# programming_module.net
KiCad netlist of a schematic drawn in Altium Designer
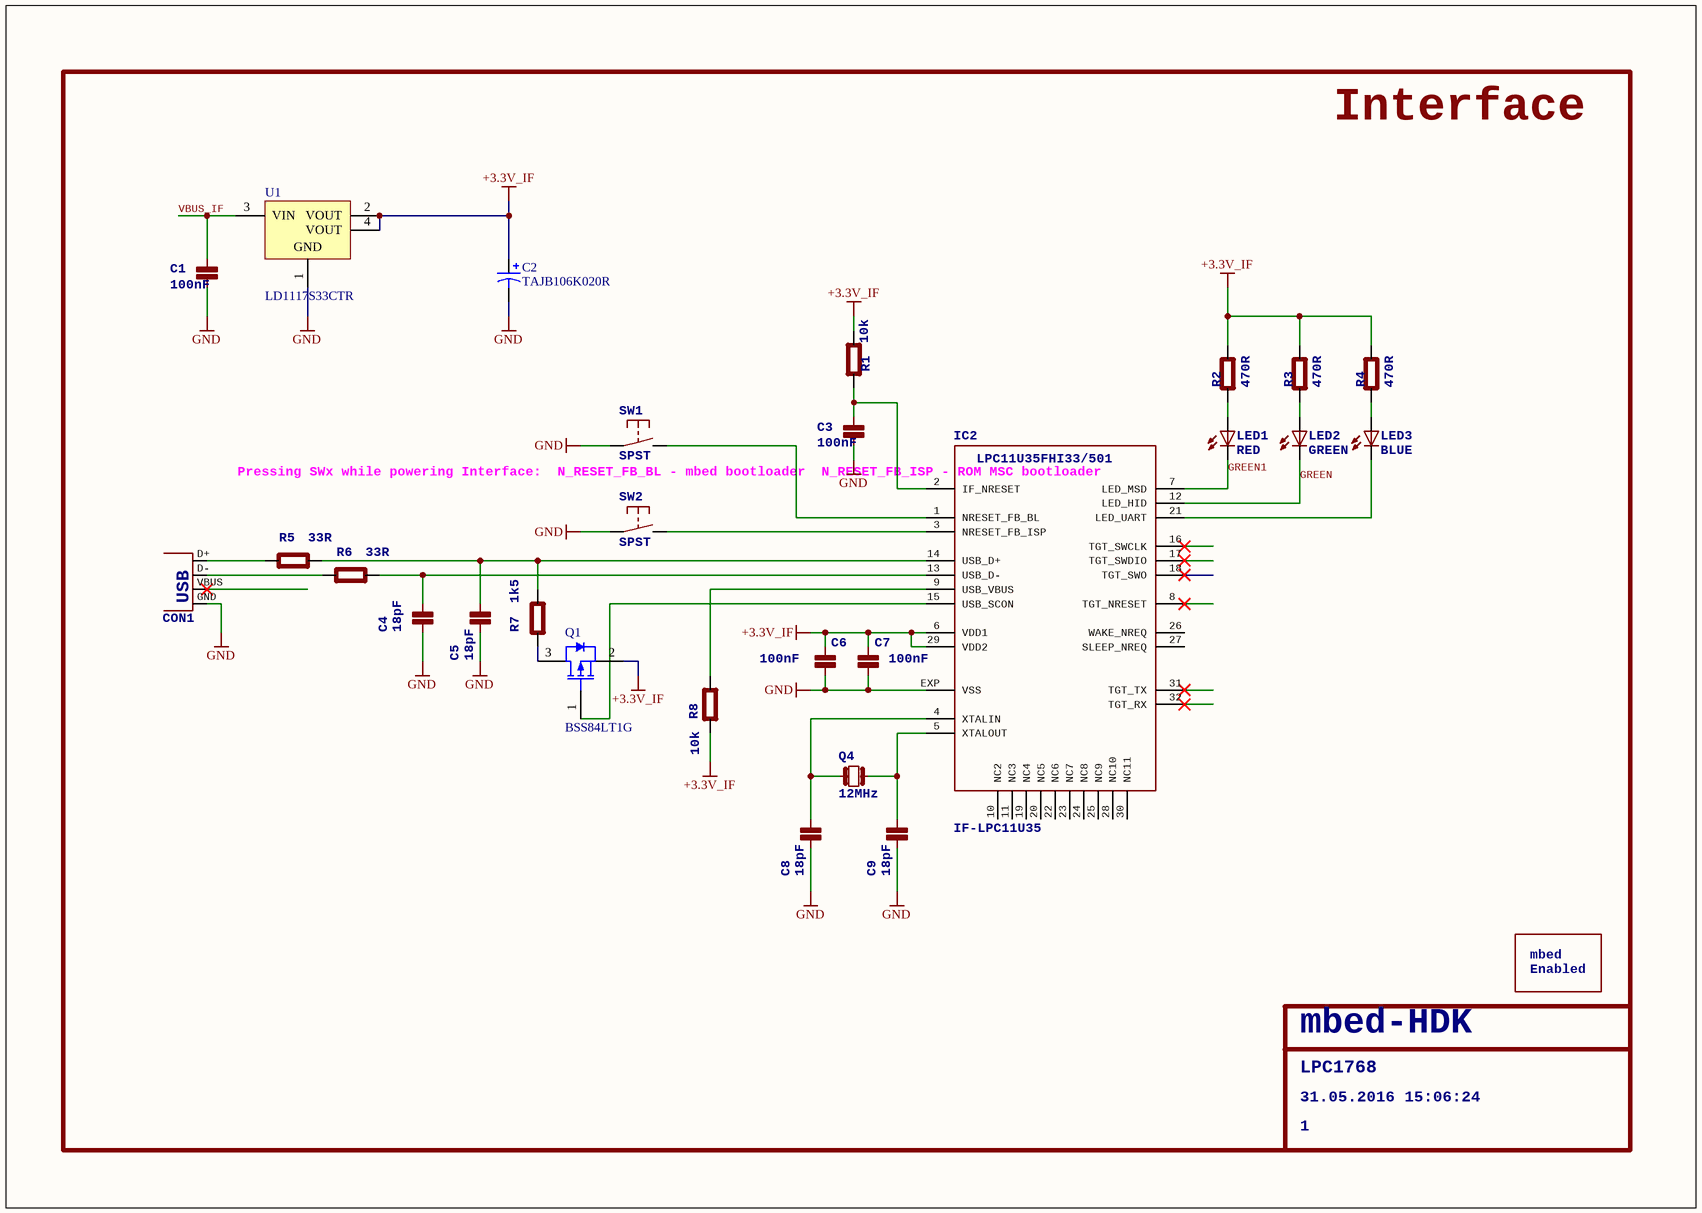
[diagram p0: programming_module.SchDoc]

(export (version "E")
  (design (tool "Eeschema 10.0.6"))
  (components
    (comp (ref "C1") (value "100nF") (footprint "0603") (libsource (lib "") (part "C0603_1")))
    (comp (ref "C2")
      (value "TAJB106K020R")
      (footprint "AVX-CAPC3528_V")
      (description "Capacitor, Tantalum, 10uF 10% 20V MCCT-B (3528)")
      (fields (field (name "MANUFACTURER") "AVX") (field (name "TOLERANCE") "10%"))
      (libsource (lib "Altium Content Vault") (part "AVX-CAP-P-2"))
    )
    (comp (ref "C3") (value "100nF") (footprint "0603") (libsource (lib "") (part "C0603_1")))
    (comp (ref "C4") (value "18pF") (footprint "0603") (libsource (lib "mbed-HDK") (part "C0603")))
    (comp (ref "C5") (value "18pF") (footprint "0603") (libsource (lib "mbed-HDK") (part "C0603")))
    (comp (ref "C6") (value "100nF") (footprint "0603") (libsource (lib "") (part "C0603_1")))
    (comp (ref "C7") (value "100nF") (footprint "0603") (libsource (lib "") (part "C0603_1")))
    (comp (ref "C8") (value "18pF") (footprint "0603") (libsource (lib "mbed-HDK") (part "C0603")))
    (comp (ref "C9") (value "18pF") (footprint "0603") (libsource (lib "mbed-HDK") (part "C0603")))
    (comp (ref "CON1")
      (value "USB-MB-S")
      (footprint "USB-MB-S")
      (description "USB Connectors")
      (fields (field (name "USB") "USB"))
      (libsource (lib "mbed-HDK") (part "USB-MB-S"))
    )
    (comp (ref "IC2")
      (value "IF-LPC11U35")
      (footprint "HVQFN33")
      (fields (field (name "LPC11U35FHI33/501") "LPC11U35FHI33/501"))
      (libsource (lib "mbed-HDK") (part "IF-LPC11U35"))
    )
    (comp (ref "LED1") (value "RED") (footprint "CHIPLED_0603") (libsource (lib "mbed-HDK") (part "LED0603")))
    (comp (ref "LED2")
      (value "GREEN")
      (footprint "CHIPLED_0603")
      (libsource (lib "mbed-HDK") (part "LED0603"))
    )
    (comp (ref "LED3")
      (value "BLUE")
      (footprint "CHIPLED_0603")
      (libsource (lib "mbed-HDK") (part "LED0603"))
    )
    (comp (ref "Q1")
      (value "BSS84LT1G")
      (footprint "ONSC-SOT-23-3-318-08_V")
      (description "Power MOSFET Single P-Channel, -50 V, 10 Ohm, 3-Pin SOT-23, Pb-Free, Tape and Reel")
      (fields (field (name "MANUFACTURER") "On Semiconductor"))
      (libsource (lib "Altium Content Vault") (part "ONSC-PMOS-G1S2D3-3_D"))
    )
    (comp (ref "Q4") (value "12MHz") (footprint "HC49UP") (libsource (lib "mbed-HDK") (part "Q_HC49UP")))
    (comp (ref "R1") (value "10k") (footprint "0603") (libsource (lib "mbed-HDK") (part "R0603")))
    (comp (ref "R2") (value "470R") (footprint "0603") (libsource (lib "mbed-HDK") (part "R0603")))
    (comp (ref "R3") (value "470R") (footprint "0603") (libsource (lib "mbed-HDK") (part "R0603")))
    (comp (ref "R4") (value "470R") (footprint "0603") (libsource (lib "mbed-HDK") (part "R0603")))
    (comp (ref "R5") (value "33R") (footprint "0603") (libsource (lib "mbed-HDK") (part "R0603")))
    (comp (ref "R6") (value "33R") (footprint "0603") (libsource (lib "mbed-HDK") (part "R0603")))
    (comp (ref "R7") (value "1k5") (footprint "0603") (libsource (lib "mbed-HDK") (part "R0603")))
    (comp (ref "R8") (value "10k") (footprint "0603") (libsource (lib "mbed-HDK") (part "R0603")))
    (comp (ref "SS1")
      (value "MBED-ENABLED-LOGOMEDIUM")
      (footprint "MBED-ENABLED-LOGO-500X500-MIL")
      (fields (field (name "MBED") "mbed") (field (name "ENABLED") "Enabled"))
      (libsource (lib "mbed-HDK") (part "MBED-ENABLED-LOGOMEDIUM"))
    )
    (comp (ref "SW1") (value "SPST") (footprint "DTSM-32S-B") (libsource (lib "mbed-HDK") (part "SPST")))
    (comp (ref "SW2") (value "SPST") (footprint "DTSM-32S-B") (libsource (lib "mbed-HDK") (part "SPST")))
    (comp (ref "U1")
      (value "LD1117S33CTR")
      (footprint "SOT-223_L")
      (description "Fixed Low Drop Positive Voltage Regulator, 3.3V, 4-Pin SOT-223, Tape and Reel")
      (libsource (lib "Altium Content Vault") (part "PM-REG-LD1117-SOT4"))
    )
  )
  (nets
    (net (code "1") (name "+3.3V_IF") (class "Default")
      (node (ref "C2") (pin "1") (pinfunction "1_1") (pintype "passive"))
      (node (ref "C6") (pin "1") (pinfunction "P$1_1") (pintype "passive"))
      (node (ref "C7") (pin "1") (pinfunction "P$1_1") (pintype "passive"))
      (node (ref "IC2") (pin "29") (pinfunction "VDD2_29") (pintype "passive"))
      (node (ref "IC2") (pin "6") (pinfunction "VDD1_6") (pintype "passive"))
      (node (ref "Q1") (pin "2") (pinfunction "S_2") (pintype "passive"))
      (node (ref "R1") (pin "2") (pinfunction "P$2_2") (pintype "passive"))
      (node (ref "R2") (pin "1") (pinfunction "P$1_1") (pintype "passive"))
      (node (ref "R3") (pin "1") (pinfunction "P$1_1") (pintype "passive"))
      (node (ref "R4") (pin "1") (pinfunction "P$1_1") (pintype "passive"))
      (node (ref "R8") (pin "2") (pinfunction "P$2_2") (pintype "passive"))
      (node (ref "U1") (pin "2") (pinfunction "VOUT_2") (pintype "power_in"))
      (node (ref "U1") (pin "4") (pinfunction "VOUT_4") (pintype "power_in"))
    )
    (net (code "2") (name "/GREEN") (class "Default")
      (node (ref "IC2") (pin "12") (pinfunction "LED_HID_12") (pintype "passive"))
      (node (ref "LED2") (pin "C") (pinfunction "C_C") (pintype "passive"))
    )
    (net (code "3") (name "/GREEN1") (class "Default")
      (node (ref "IC2") (pin "7") (pinfunction "LED_MSD_7") (pintype "passive"))
      (node (ref "LED1") (pin "C") (pinfunction "C_C") (pintype "passive"))
    )
    (net (code "4") (name "/VBUS_IF") (class "Default")
      (node (ref "C1") (pin "1") (pinfunction "P$1_1") (pintype "passive"))
      (node (ref "U1") (pin "3") (pinfunction "VIN_3") (pintype "power_in"))
    )
    (net (code "5") (name "GND") (class "Default")
      (node (ref "C1") (pin "2") (pinfunction "P$2_2") (pintype "passive"))
      (node (ref "C2") (pin "2") (pinfunction "2_2") (pintype "passive"))
      (node (ref "C3") (pin "2") (pinfunction "P$2_2") (pintype "passive"))
      (node (ref "C4") (pin "2") (pinfunction "P$2_2") (pintype "passive"))
      (node (ref "C5") (pin "2") (pinfunction "P$2_2") (pintype "passive"))
      (node (ref "C6") (pin "2") (pinfunction "P$2_2") (pintype "passive"))
      (node (ref "C7") (pin "2") (pinfunction "P$2_2") (pintype "passive"))
      (node (ref "C8") (pin "2") (pinfunction "P$2_2") (pintype "passive"))
      (node (ref "C9") (pin "2") (pinfunction "P$2_2") (pintype "passive"))
      (node (ref "CON1") (pin "GND") (pinfunction "GND_GND") (pintype "passive"))
      (node (ref "IC2") (pin "EXP") (pinfunction "VSS_EXP") (pintype "passive"))
      (node (ref "SW1") (pin "P$1") (pinfunction "P_P$1") (pintype "passive"))
      (node (ref "SW2") (pin "P$1") (pinfunction "P_P$1") (pintype "passive"))
      (node (ref "U1") (pin "1") (pinfunction "GND_1") (pintype "power_in"))
    )
    (net (code "6") (name "Net-(C3-P$1)") (class "Default")
      (node (ref "C3") (pin "1") (pinfunction "P$1_1") (pintype "passive"))
      (node (ref "IC2") (pin "2") (pinfunction "IF_NRESET_2") (pintype "passive"))
      (node (ref "R1") (pin "1") (pinfunction "P$1_1") (pintype "passive"))
    )
    (net (code "7") (name "Net-(C4-P$1)") (class "Default")
      (node (ref "C4") (pin "1") (pinfunction "P$1_1") (pintype "passive"))
      (node (ref "IC2") (pin "13") (pinfunction "USB_D-_13") (pintype "passive"))
      (node (ref "R6") (pin "2") (pinfunction "P$2_2") (pintype "passive"))
    )
    (net (code "8") (name "Net-(C5-P$1)") (class "Default")
      (node (ref "C5") (pin "1") (pinfunction "P$1_1") (pintype "passive"))
      (node (ref "IC2") (pin "14") (pinfunction "USB_D+_14") (pintype "passive"))
      (node (ref "R5") (pin "2") (pinfunction "P$2_2") (pintype "passive"))
      (node (ref "R7") (pin "2") (pinfunction "P$2_2") (pintype "passive"))
    )
    (net (code "9") (name "Net-(C8-P$1)") (class "Default")
      (node (ref "C8") (pin "1") (pinfunction "P$1_1") (pintype "passive"))
      (node (ref "IC2") (pin "4") (pinfunction "XTALIN_4") (pintype "passive"))
      (node (ref "Q4") (pin "1") (pinfunction "1_1") (pintype "passive"))
    )
    (net (code "10") (name "Net-(C9-P$1)") (class "Default")
      (node (ref "C9") (pin "1") (pinfunction "P$1_1") (pintype "passive"))
      (node (ref "IC2") (pin "5") (pinfunction "XTALOUT_5") (pintype "passive"))
      (node (ref "Q4") (pin "2") (pinfunction "2_2") (pintype "passive"))
    )
    (net (code "11") (name "Net-(IC2-LED_UART)") (class "Default")
      (node (ref "IC2") (pin "21") (pinfunction "LED_UART_21") (pintype "passive"))
      (node (ref "LED3") (pin "C") (pinfunction "C_C") (pintype "passive"))
    )
    (net (code "12") (name "Net-(IC2-NRESET_FB_BL)") (class "Default")
      (node (ref "IC2") (pin "1") (pinfunction "NRESET_FB_BL_1") (pintype "passive"))
      (node (ref "SW1") (pin "P$2") (pinfunction "S_P$2") (pintype "passive"))
    )
    (net (code "13") (name "Net-(IC2-NRESET_FB_ISP)") (class "Default")
      (node (ref "IC2") (pin "3") (pinfunction "NRESET_FB_ISP_3") (pintype "passive"))
      (node (ref "SW2") (pin "P$2") (pinfunction "S_P$2") (pintype "passive"))
    )
    (net (code "14") (name "Net-(IC2-USB_SCON)") (class "Default")
      (node (ref "IC2") (pin "15") (pinfunction "USB_SCON_15") (pintype "passive"))
      (node (ref "Q1") (pin "1") (pinfunction "G_1") (pintype "passive"))
    )
    (net (code "15") (name "Net-(IC2-USB_VBUS)") (class "Default")
      (node (ref "IC2") (pin "9") (pinfunction "USB_VBUS_9") (pintype "passive"))
      (node (ref "R8") (pin "1") (pinfunction "P$1_1") (pintype "passive"))
    )
    (net (code "16") (name "Net-(Q1-D)") (class "Default")
      (node (ref "Q1") (pin "3") (pinfunction "D_3") (pintype "passive"))
      (node (ref "R7") (pin "1") (pinfunction "P$1_1") (pintype "passive"))
    )
    (net (code "17") (name "Net-(R2-P$2)") (class "Default")
      (node (ref "LED1") (pin "A") (pinfunction "A_A") (pintype "passive"))
      (node (ref "R2") (pin "2") (pinfunction "P$2_2") (pintype "passive"))
    )
    (net (code "18") (name "Net-(R3-P$2)") (class "Default")
      (node (ref "LED2") (pin "A") (pinfunction "A_A") (pintype "passive"))
      (node (ref "R3") (pin "2") (pinfunction "P$2_2") (pintype "passive"))
    )
    (net (code "19") (name "Net-(R4-P$2)") (class "Default")
      (node (ref "LED3") (pin "A") (pinfunction "A_A") (pintype "passive"))
      (node (ref "R4") (pin "2") (pinfunction "P$2_2") (pintype "passive"))
    )
    (net (code "20") (name "Net-(R5-P$1)") (class "Default")
      (node (ref "CON1") (pin "D+") (pinfunction "D+_D+") (pintype "passive"))
      (node (ref "R5") (pin "1") (pinfunction "P$1_1") (pintype "passive"))
    )
    (net (code "21") (name "Net-(R6-P$1)") (class "Default")
      (node (ref "CON1") (pin "D-") (pinfunction "D-_D-") (pintype "passive"))
      (node (ref "R6") (pin "1") (pinfunction "P$1_1") (pintype "passive"))
    )
    (net (code "22") (name "unconnected-(CON1-PadVBUS)") (class "Default")
      (node (ref "CON1") (pin "VBUS") (pinfunction "VBUS_VBUS") (pintype "passive+no_connect"))
    )
    (net (code "23") (name "unconnected-(IC2-NC2-Pad10)") (class "Default")
      (node (ref "IC2") (pin "10") (pinfunction "NC2_10") (pintype "passive"))
    )
    (net (code "24") (name "unconnected-(IC2-NC3-Pad11)") (class "Default")
      (node (ref "IC2") (pin "11") (pinfunction "NC3_11") (pintype "passive"))
    )
    (net (code "25") (name "unconnected-(IC2-NC4-Pad19)") (class "Default")
      (node (ref "IC2") (pin "19") (pinfunction "NC4_19") (pintype "passive"))
    )
    (net (code "26") (name "unconnected-(IC2-NC5-Pad20)") (class "Default")
      (node (ref "IC2") (pin "20") (pinfunction "NC5_20") (pintype "passive"))
    )
    (net (code "27") (name "unconnected-(IC2-NC6-Pad22)") (class "Default")
      (node (ref "IC2") (pin "22") (pinfunction "NC6_22") (pintype "passive"))
    )
    (net (code "28") (name "unconnected-(IC2-NC7-Pad23)") (class "Default")
      (node (ref "IC2") (pin "23") (pinfunction "NC7_23") (pintype "passive"))
    )
    (net (code "29") (name "unconnected-(IC2-NC8-Pad24)") (class "Default")
      (node (ref "IC2") (pin "24") (pinfunction "NC8_24") (pintype "passive"))
    )
    (net (code "30") (name "unconnected-(IC2-NC9-Pad25)") (class "Default")
      (node (ref "IC2") (pin "25") (pinfunction "NC9_25") (pintype "passive"))
    )
    (net (code "31") (name "unconnected-(IC2-NC10-Pad28)") (class "Default")
      (node (ref "IC2") (pin "28") (pinfunction "NC10_28") (pintype "passive"))
    )
    (net (code "32") (name "unconnected-(IC2-NC11-Pad30)") (class "Default")
      (node (ref "IC2") (pin "30") (pinfunction "NC11_30") (pintype "passive"))
    )
    (net (code "33") (name "unconnected-(IC2-SLEEP_NREQ-Pad27)") (class "Default")
      (node (ref "IC2") (pin "27") (pinfunction "SLEEP_NREQ_27") (pintype "passive"))
    )
    (net (code "34") (name "unconnected-(IC2-TGT_NRESET-Pad8)") (class "Default")
      (node (ref "IC2") (pin "8") (pinfunction "TGT_NRESET_8") (pintype "passive+no_connect"))
    )
    (net (code "35") (name "unconnected-(IC2-TGT_RX-Pad32)") (class "Default")
      (node (ref "IC2") (pin "32") (pinfunction "TGT_RX_32") (pintype "passive+no_connect"))
    )
    (net (code "36") (name "unconnected-(IC2-TGT_SWCLK-Pad16)") (class "Default")
      (node (ref "IC2") (pin "16") (pinfunction "TGT_SWCLK_16") (pintype "passive+no_connect"))
    )
    (net (code "37") (name "unconnected-(IC2-TGT_SWDIO-Pad17)") (class "Default")
      (node (ref "IC2") (pin "17") (pinfunction "TGT_SWDIO_17") (pintype "passive+no_connect"))
    )
    (net (code "38") (name "unconnected-(IC2-TGT_SWO-Pad18)") (class "Default")
      (node (ref "IC2") (pin "18") (pinfunction "TGT_SWO_18") (pintype "passive+no_connect"))
    )
    (net (code "39") (name "unconnected-(IC2-TGT_TX-Pad31)") (class "Default")
      (node (ref "IC2") (pin "31") (pinfunction "TGT_TX_31") (pintype "passive+no_connect"))
    )
    (net (code "40") (name "unconnected-(IC2-WAKE_NREQ-Pad26)") (class "Default")
      (node (ref "IC2") (pin "26") (pinfunction "WAKE_NREQ_26") (pintype "passive"))
    )
  )
)
